# USBtoUART.net
KiCad netlist of a schematic drawn in Altium Designer
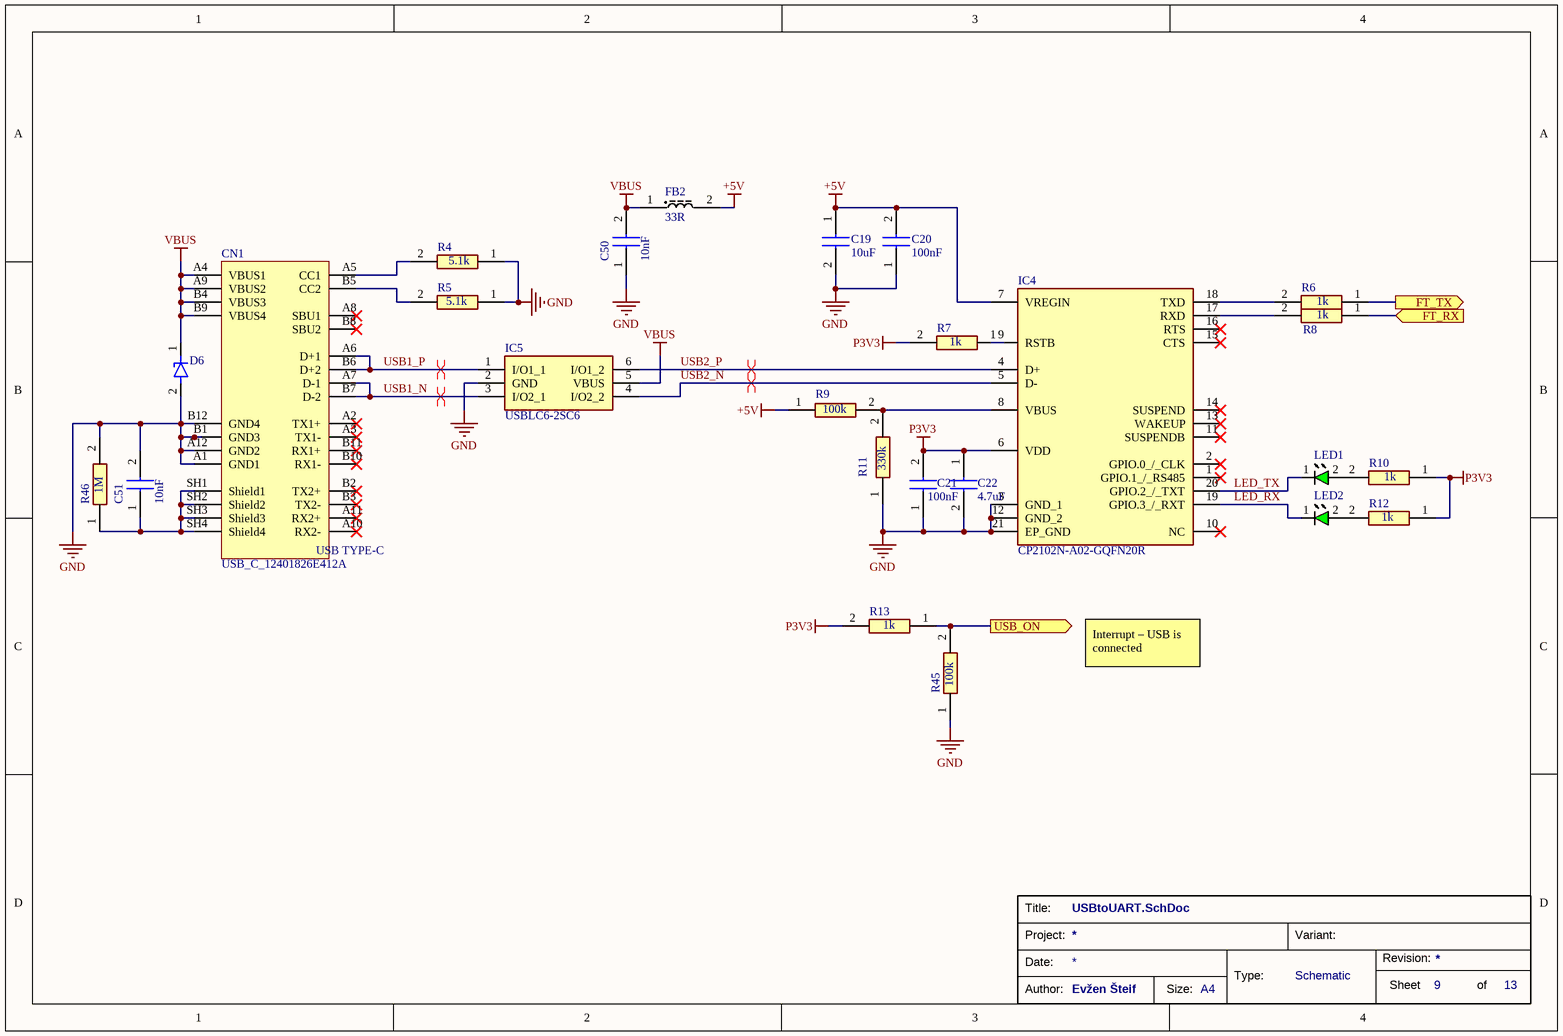
[diagram p0: USBtoUART.SchDoc]

(export (version "E")
  (design (tool "Eeschema 10.0.6"))
  (components
    (comp (ref "C19")
      (value "10uF")
      (footprint "SamacSys:GRM18x")
      (description "Capacitor")
      (fields
        (field (name "MANUFACTURER_PART_NUMBER") "GRM188R61E106KA73D")
        (field (name "MOUSER PART NUMBER") "81-GRM188R61E106KA3D")
      )
      (libsource (lib "*") (part "GRM188R61E106KA73D"))
    )
    (comp (ref "C20")
      (value "100nF")
      (footprint "SamacSys:CAPC1005X70N")
      (description "Capacitor")
      (fields
        (field (name "MANUFACTURER_PART_NUMBER") "GRM155R61A104KA01D")
        (field (name "MOUSER PART NUMBER") "81-GRM155R61A104KA01")
      )
      (libsource (lib "*") (part "GRM155R61A104KA01D"))
    )
    (comp (ref "C21")
      (value "100nF")
      (footprint "SamacSys:CAPC1005X70N")
      (description "Capacitor")
      (fields
        (field (name "MANUFACTURER_PART_NUMBER") "GRM155R61A104KA01D")
        (field (name "MOUSER PART NUMBER") "81-GRM155R61A104KA01")
      )
      (libsource (lib "*") (part "GRM155R61A104KA01D"))
    )
    (comp (ref "C22")
      (value "4.7uF")
      (footprint "SamacSys:CAPC1608X90N")
      (description "Capacitor")
      (fields
        (field (name "MANUFACTURER_PART_NUMBER") "GRM188R61E475KE11J")
        (field (name "MOUSER PART NUMBER") "81-GRM188R61E475KE1J")
      )
      (libsource (lib "*") (part "GRM188R61E475KE11J"))
    )
    (comp (ref "C50")
      (value "10nF")
      (footprint "SamacSys:GRM15x")
      (description "Capacitor")
      (fields
        (field (name "MANUFACTURER_PART_NUMBER") "GRM155R71H103KA88D")
        (field (name "MOUSER PART NUMBER") "81-GRM155R71H103KA8D")
      )
      (libsource (lib "SamacSys") (part "GRM155R71H103KA88D"))
    )
    (comp (ref "C51")
      (value "10nF")
      (footprint "SamacSys:GRM15x")
      (description "Capacitor")
      (fields
        (field (name "MANUFACTURER_PART_NUMBER") "GRM155R71H103KA88D")
        (field (name "MOUSER PART NUMBER") "81-GRM155R71H103KA8D")
      )
      (libsource (lib "SamacSys") (part "GRM155R71H103KA88D"))
    )
    (comp (ref "CN1")
      (value "USB_C_12401826E412A")
      (footprint "SamacSys:CON_USB-TYPEC_AMPHENOL_12401826E412A")
      (description "USB_TypeC, 24 pins, RA, SMD, T=2.96mm (USB Certified 3.1)")
      (fields (field (name "INTERNAL_PART_NUMBER") "MCD-03232") (field (name "MANUFACTURER") "AMPHENOL ICC"))
      (libsource (lib "SamacSys") (part "MCD-03232"))
    )
    (comp (ref "D6")
      (value "ESDA25P35-1U1M")
      (footprint "SamacSys:ESDA25P351U1M")
      (description "TVS Diode (Uni-directional)")
      (fields (field (name "MOUSER PART NUMBER") "511-ESDA25P35-1U1M"))
      (libsource (lib "SamacSys") (part "ESDA25P35-1U1M"))
    )
    (comp (ref "FB2")
      (value "33R")
      (footprint "SamacSys:BLM18SP221SN1B")
      (description "Ferrite Bead")
      (fields
        (field (name "MANUFACTURER_PART_NUMBER") "BLM18SG330SN1D")
        (field (name "MOUSER PART NUMBER") "81-BLM18SG330SN1D")
      )
      (libsource (lib "SamacSys") (part "BLM18SG330SN1D"))
    )
    (comp (ref "IC4")
      (value "CP2102N-A02-GQFN20R")
      (footprint "SamacSys:CP2102NA02GQFN20")
      (description "Integrated Circuit")
      (fields (field (name "MOUSER PART NUMBER") "634-CP2102NA02QFN20R"))
      (libsource (lib "SamacSys") (part "CP2102N-A02-GQFN20R"))
    )
    (comp (ref "IC5")
      (value "USBLC6-2SC6")
      (footprint "SamacSys:SOT95P280X145-6N")
      (description "Integrated Circuit")
      (fields (field (name "MOUSER PART NUMBER") "511-USBLC6-2SC6"))
      (libsource (lib "SamacSys") (part "USBLC6-2SC6"))
    )
    (comp (ref "LED1")
      (value "150060GS75000")
      (footprint "SamacSys:LEDC1608X80N")
      (description "LED")
      (fields (field (name "MOUSER PART NUMBER") "710-150060GS75000"))
      (libsource (lib "SamacSys") (part "150060GS75000"))
    )
    (comp (ref "LED2")
      (value "150060GS75000")
      (footprint "SamacSys:LEDC1608X80N")
      (description "LED")
      (fields (field (name "MOUSER PART NUMBER") "710-150060GS75000"))
      (libsource (lib "SamacSys") (part "150060GS75000"))
    )
    (comp (ref "R4")
      (value "5.1k")
      (footprint "SamacSys:RESC1005X35N")
      (description "Resistor")
      (fields (field (name "MANUFACTURER_PART_NUMBER") "RT0402FRE075K1L"))
      (libsource (lib "SamacSys") (part "RT0402FRE075K1L"))
    )
    (comp (ref "R5")
      (value "5.1k")
      (footprint "SamacSys:RESC1005X35N")
      (description "Resistor")
      (fields (field (name "MANUFACTURER_PART_NUMBER") "RT0402FRE075K1L"))
      (libsource (lib "SamacSys") (part "RT0402FRE075K1L"))
    )
    (comp (ref "R6")
      (value "1k")
      (footprint "SamacSys:RESC1005X35N")
      (description "Resistor")
      (fields
        (field (name "MANUFACTURER_PART_NUMBER") "RT0402FRE071KL")
        (field (name "ARROW PART NUMBER") "RT0402FRE07100KL")
      )
      (libsource (lib "SamacSys") (part "RT0402FRE071KL"))
    )
    (comp (ref "R7")
      (value "1k")
      (footprint "SamacSys:RESC1005X35N")
      (description "Resistor")
      (fields
        (field (name "MANUFACTURER_PART_NUMBER") "RT0402FRE071KL")
        (field (name "ARROW PART NUMBER") "RT0402FRE07100KL")
      )
      (libsource (lib "SamacSys") (part "RT0402FRE071KL"))
    )
    (comp (ref "R8")
      (value "1k")
      (footprint "SamacSys:RESC1005X35N")
      (description "Resistor")
      (fields
        (field (name "MANUFACTURER_PART_NUMBER") "RT0402FRE071KL")
        (field (name "ARROW PART NUMBER") "RT0402FRE07100KL")
      )
      (libsource (lib "SamacSys") (part "RT0402FRE071KL"))
    )
    (comp (ref "R9")
      (value "100k")
      (footprint "SamacSys:RESC1005X40N")
      (description "Resistor")
      (fields (field (name "MANUFACTURER_PART_NUMBER") "RC0402BR-07100KL"))
      (libsource (lib "SamacSys") (part "RC0402BR-07100KL"))
    )
    (comp (ref "R10")
      (value "1k")
      (footprint "SamacSys:RESC1005X35N")
      (description "Resistor")
      (fields
        (field (name "MANUFACTURER_PART_NUMBER") "RT0402FRE071KL")
        (field (name "ARROW PART NUMBER") "RT0402FRE07100KL")
      )
      (libsource (lib "SamacSys") (part "RT0402FRE071KL"))
    )
    (comp (ref "R11")
      (value "330k")
      (footprint "SamacSys:RESC1005X40N")
      (description "Resistor")
      (fields (field (name "MANUFACTURER_PART_NUMBER") "RC0402BR-07330KL"))
      (libsource (lib "SamacSys") (part "RC0402BR-07330KL"))
    )
    (comp (ref "R12")
      (value "1k")
      (footprint "SamacSys:RESC1005X35N")
      (description "Resistor")
      (fields
        (field (name "MANUFACTURER_PART_NUMBER") "RT0402FRE071KL")
        (field (name "ARROW PART NUMBER") "RT0402FRE07100KL")
      )
      (libsource (lib "SamacSys") (part "RT0402FRE071KL"))
    )
    (comp (ref "R13")
      (value "1k")
      (footprint "SamacSys:RESC1005X35N")
      (description "Resistor")
      (fields
        (field (name "MANUFACTURER_PART_NUMBER") "RT0402FRE071KL")
        (field (name "ARROW PART NUMBER") "RT0402FRE07100KL")
      )
      (libsource (lib "SamacSys") (part "RT0402FRE071KL"))
    )
    (comp (ref "R45")
      (value "100k")
      (footprint "SamacSys:RESC1005X40N")
      (description "Resistor")
      (fields (field (name "MANUFACTURER_PART_NUMBER") "RC0402BR-07100KL"))
      (libsource (lib "") (part "RC0402BR-07100KL_1"))
    )
    (comp (ref "R46")
      (value "1M")
      (footprint "SamacSys:RESC1005X40N")
      (description "Resistor")
      (fields
        (field (name "MANUFACTURER_PART_NUMBER") "RC0402FR-071ML")
        (field (name "MOUSER PART NUMBER") "603-RC0402FR-071ML")
      )
      (libsource (lib "*") (part "RC0402FR-071ML"))
    )
  )
  (nets
    (net (code "1") (name "+5V") (class "Default")
      (node (ref "C19") (pin "1") (pinfunction "1_1") (pintype "passive"))
      (node (ref "C20") (pin "2") (pinfunction "2_2") (pintype "passive"))
      (node (ref "FB2") (pin "2") (pinfunction "2_2") (pintype "passive"))
      (node (ref "IC4") (pin "7") (pinfunction "VREGIN_7") (pintype "passive"))
      (node (ref "R9") (pin "1") (pinfunction "1_1") (pintype "passive"))
    )
    (net (code "2") (name "/FT_RX") (class "Default")
      (node (ref "R8") (pin "1") (pinfunction "1_1") (pintype "passive"))
    )
    (net (code "3") (name "/FT_TX") (class "Default")
      (node (ref "R6") (pin "1") (pinfunction "1_1") (pintype "passive"))
    )
    (net (code "4") (name "/LED_RX") (class "Default")
      (node (ref "IC4") (pin "19") (pinfunction "GPIO.3_/_RXT_19") (pintype "passive"))
      (node (ref "LED2") (pin "1") (pinfunction "K_1") (pintype "passive"))
    )
    (net (code "5") (name "/LED_TX") (class "Default")
      (node (ref "IC4") (pin "20") (pinfunction "GPIO.2_/_TXT_20") (pintype "passive"))
      (node (ref "LED1") (pin "1") (pinfunction "K_1") (pintype "passive"))
    )
    (net (code "6") (name "/USB1_N") (class "Default")
      (node (ref "CN1") (pin "A7") (pinfunction "D-1_A7") (pintype "passive"))
      (node (ref "CN1") (pin "B7") (pinfunction "D-2_B7") (pintype "passive"))
      (node (ref "IC5") (pin "3") (pinfunction "I/O2_1_3") (pintype "passive"))
    )
    (net (code "7") (name "/USB1_P") (class "Default")
      (node (ref "CN1") (pin "A6") (pinfunction "D+1_A6") (pintype "passive"))
      (node (ref "CN1") (pin "B6") (pinfunction "D+2_B6") (pintype "passive"))
      (node (ref "IC5") (pin "1") (pinfunction "I/O1_1_1") (pintype "passive"))
    )
    (net (code "8") (name "/USB2_N") (class "Default")
      (node (ref "IC4") (pin "5") (pinfunction "D-_5") (pintype "passive"))
      (node (ref "IC5") (pin "4") (pinfunction "I/O2_2_4") (pintype "passive"))
    )
    (net (code "9") (name "/USB2_P") (class "Default")
      (node (ref "IC4") (pin "4") (pinfunction "D+_4") (pintype "passive"))
      (node (ref "IC5") (pin "6") (pinfunction "I/O1_2_6") (pintype "passive"))
    )
    (net (code "10") (name "/USB_ON") (class "Default")
      (node (ref "R13") (pin "1") (pinfunction "1_1") (pintype "passive"))
      (node (ref "R45") (pin "2") (pinfunction "2_2") (pintype "passive"))
    )
    (net (code "11") (name "GND") (class "Default")
      (node (ref "C19") (pin "2") (pinfunction "2_2") (pintype "passive"))
      (node (ref "C20") (pin "1") (pinfunction "1_1") (pintype "passive"))
      (node (ref "C21") (pin "1") (pinfunction "1_1") (pintype "passive"))
      (node (ref "C22") (pin "2") (pinfunction "2_2") (pintype "passive"))
      (node (ref "C50") (pin "1") (pinfunction "1_1") (pintype "passive"))
      (node (ref "C51") (pin "2") (pinfunction "2_2") (pintype "passive"))
      (node (ref "CN1") (pin "A1") (pinfunction "GND1_A1") (pintype "passive"))
      (node (ref "CN1") (pin "A12") (pinfunction "GND2_A12") (pintype "passive"))
      (node (ref "CN1") (pin "B1") (pinfunction "GND3_B1") (pintype "passive"))
      (node (ref "CN1") (pin "B12") (pinfunction "GND4_B12") (pintype "passive"))
      (node (ref "D6") (pin "2") (pinfunction "A_2") (pintype "passive"))
      (node (ref "IC4") (pin "12") (pinfunction "GND_2_12") (pintype "passive"))
      (node (ref "IC4") (pin "21") (pinfunction "EP_GND_21") (pintype "passive"))
      (node (ref "IC4") (pin "3") (pinfunction "GND_1_3") (pintype "passive"))
      (node (ref "IC5") (pin "2") (pinfunction "GND_2") (pintype "passive"))
      (node (ref "R11") (pin "1") (pinfunction "1_1") (pintype "passive"))
      (node (ref "R4") (pin "1") (pinfunction "1_1") (pintype "passive"))
      (node (ref "R45") (pin "1") (pinfunction "1_1") (pintype "passive"))
      (node (ref "R46") (pin "2") (pinfunction "2_2") (pintype "passive"))
      (node (ref "R5") (pin "1") (pinfunction "1_1") (pintype "passive"))
    )
    (net (code "12") (name "Net-(CN1-CC1)") (class "Default")
      (node (ref "CN1") (pin "A5") (pinfunction "CC1_A5") (pintype "passive"))
      (node (ref "R4") (pin "2") (pinfunction "2_2") (pintype "passive"))
    )
    (net (code "13") (name "Net-(CN1-CC2)") (class "Default")
      (node (ref "CN1") (pin "B5") (pinfunction "CC2_B5") (pintype "passive"))
      (node (ref "R5") (pin "2") (pinfunction "2_2") (pintype "passive"))
    )
    (net (code "14") (name "Net-(CN1-Shield1)") (class "Default")
      (node (ref "C51") (pin "1") (pinfunction "1_1") (pintype "passive"))
      (node (ref "CN1") (pin "SH1") (pinfunction "Shield1_SH1") (pintype "passive"))
      (node (ref "CN1") (pin "SH2") (pinfunction "Shield2_SH2") (pintype "passive"))
      (node (ref "CN1") (pin "SH3") (pinfunction "Shield3_SH3") (pintype "passive"))
      (node (ref "CN1") (pin "SH4") (pinfunction "Shield4_SH4") (pintype "passive"))
      (node (ref "R46") (pin "1") (pinfunction "1_1") (pintype "passive"))
    )
    (net (code "15") (name "Net-(IC4-RSTB)") (class "Default")
      (node (ref "IC4") (pin "9") (pinfunction "RSTB_9") (pintype "passive"))
      (node (ref "R7") (pin "1") (pinfunction "1_1") (pintype "passive"))
    )
    (net (code "16") (name "Net-(IC4-RXD)") (class "Default")
      (node (ref "IC4") (pin "17") (pinfunction "RXD_17") (pintype "passive"))
      (node (ref "R8") (pin "2") (pinfunction "2_2") (pintype "passive"))
    )
    (net (code "17") (name "Net-(IC4-TXD)") (class "Default")
      (node (ref "IC4") (pin "18") (pinfunction "TXD_18") (pintype "passive"))
      (node (ref "R6") (pin "2") (pinfunction "2_2") (pintype "passive"))
    )
    (net (code "18") (name "Net-(IC4-VBUS)") (class "Default")
      (node (ref "IC4") (pin "8") (pinfunction "VBUS_8") (pintype "passive"))
      (node (ref "R11") (pin "2") (pinfunction "2_2") (pintype "passive"))
      (node (ref "R9") (pin "2") (pinfunction "2_2") (pintype "passive"))
    )
    (net (code "19") (name "Net-(LED1-A)") (class "Default")
      (node (ref "LED1") (pin "2") (pinfunction "A_2") (pintype "passive"))
      (node (ref "R10") (pin "2") (pinfunction "2_2") (pintype "passive"))
    )
    (net (code "20") (name "Net-(LED2-A)") (class "Default")
      (node (ref "LED2") (pin "2") (pinfunction "A_2") (pintype "passive"))
      (node (ref "R12") (pin "2") (pinfunction "2_2") (pintype "passive"))
    )
    (net (code "21") (name "P3V3") (class "Default")
      (node (ref "C21") (pin "2") (pinfunction "2_2") (pintype "passive"))
      (node (ref "C22") (pin "1") (pinfunction "1_1") (pintype "passive"))
      (node (ref "IC4") (pin "6") (pinfunction "VDD_6") (pintype "passive"))
      (node (ref "R10") (pin "1") (pinfunction "1_1") (pintype "passive"))
      (node (ref "R12") (pin "1") (pinfunction "1_1") (pintype "passive"))
      (node (ref "R13") (pin "2") (pinfunction "2_2") (pintype "passive"))
      (node (ref "R7") (pin "2") (pinfunction "2_2") (pintype "passive"))
    )
    (net (code "22") (name "VBUS") (class "Default")
      (node (ref "C50") (pin "2") (pinfunction "2_2") (pintype "passive"))
      (node (ref "CN1") (pin "A4") (pinfunction "VBUS1_A4") (pintype "passive"))
      (node (ref "CN1") (pin "A9") (pinfunction "VBUS2_A9") (pintype "passive"))
      (node (ref "CN1") (pin "B4") (pinfunction "VBUS3_B4") (pintype "passive"))
      (node (ref "CN1") (pin "B9") (pinfunction "VBUS4_B9") (pintype "passive"))
      (node (ref "D6") (pin "1") (pinfunction "K_1") (pintype "passive"))
      (node (ref "FB2") (pin "1") (pinfunction "1_1") (pintype "passive"))
      (node (ref "IC5") (pin "5") (pinfunction "VBUS_5") (pintype "passive"))
    )
    (net (code "23") (name "unconnected-(CN1-RX1+-PadB11)") (class "Default")
      (node (ref "CN1") (pin "B11") (pinfunction "RX1+_B11") (pintype "passive+no_connect"))
    )
    (net (code "24") (name "unconnected-(CN1-RX1--PadB10)") (class "Default")
      (node (ref "CN1") (pin "B10") (pinfunction "RX1-_B10") (pintype "passive+no_connect"))
    )
    (net (code "25") (name "unconnected-(CN1-RX2+-PadA11)") (class "Default")
      (node (ref "CN1") (pin "A11") (pinfunction "RX2+_A11") (pintype "passive+no_connect"))
    )
    (net (code "26") (name "unconnected-(CN1-RX2--PadA10)") (class "Default")
      (node (ref "CN1") (pin "A10") (pinfunction "RX2-_A10") (pintype "passive+no_connect"))
    )
    (net (code "27") (name "unconnected-(CN1-SBU1-PadA8)") (class "Default")
      (node (ref "CN1") (pin "A8") (pinfunction "SBU1_A8") (pintype "passive+no_connect"))
    )
    (net (code "28") (name "unconnected-(CN1-SBU2-PadB8)") (class "Default")
      (node (ref "CN1") (pin "B8") (pinfunction "SBU2_B8") (pintype "passive+no_connect"))
    )
    (net (code "29") (name "unconnected-(CN1-TX1+-PadA2)") (class "Default")
      (node (ref "CN1") (pin "A2") (pinfunction "TX1+_A2") (pintype "passive+no_connect"))
    )
    (net (code "30") (name "unconnected-(CN1-TX1--PadA3)") (class "Default")
      (node (ref "CN1") (pin "A3") (pinfunction "TX1-_A3") (pintype "passive+no_connect"))
    )
    (net (code "31") (name "unconnected-(CN1-TX2+-PadB2)") (class "Default")
      (node (ref "CN1") (pin "B2") (pinfunction "TX2+_B2") (pintype "passive+no_connect"))
    )
    (net (code "32") (name "unconnected-(CN1-TX2--PadB3)") (class "Default")
      (node (ref "CN1") (pin "B3") (pinfunction "TX2-_B3") (pintype "passive+no_connect"))
    )
    (net (code "33") (name "unconnected-(IC4-CTS-Pad15)") (class "Default")
      (node (ref "IC4") (pin "15") (pinfunction "CTS_15") (pintype "passive+no_connect"))
    )
    (net (code "34") (name "unconnected-(IC4-GPIO.0_{slash}_CLK-Pad2)") (class "Default")
      (node (ref "IC4") (pin "2") (pinfunction "GPIO.0_/_CLK_2") (pintype "passive+no_connect"))
    )
    (net (code "35") (name "unconnected-(IC4-GPIO.1_{slash}_RS485-Pad1)") (class "Default")
      (node (ref "IC4") (pin "1") (pinfunction "GPIO.1_/_RS485_1") (pintype "passive+no_connect"))
    )
    (net (code "36") (name "unconnected-(IC4-NC-Pad10)") (class "Default")
      (node (ref "IC4") (pin "10") (pinfunction "NC_10") (pintype "passive+no_connect"))
    )
    (net (code "37") (name "unconnected-(IC4-RTS-Pad16)") (class "Default")
      (node (ref "IC4") (pin "16") (pinfunction "RTS_16") (pintype "passive+no_connect"))
    )
    (net (code "38") (name "unconnected-(IC4-SUSPEND-Pad14)") (class "Default")
      (node (ref "IC4") (pin "14") (pinfunction "SUSPEND_14") (pintype "passive+no_connect"))
    )
    (net (code "39") (name "unconnected-(IC4-SUSPENDB-Pad11)") (class "Default")
      (node (ref "IC4") (pin "11") (pinfunction "SUSPENDB_11") (pintype "passive+no_connect"))
    )
    (net (code "40") (name "unconnected-(IC4-WAKEUP-Pad13)") (class "Default")
      (node (ref "IC4") (pin "13") (pinfunction "WAKEUP_13") (pintype "passive+no_connect"))
    )
  )
)
